# firefly.net
KiCad netlist of a schematic drawn in EAGLE
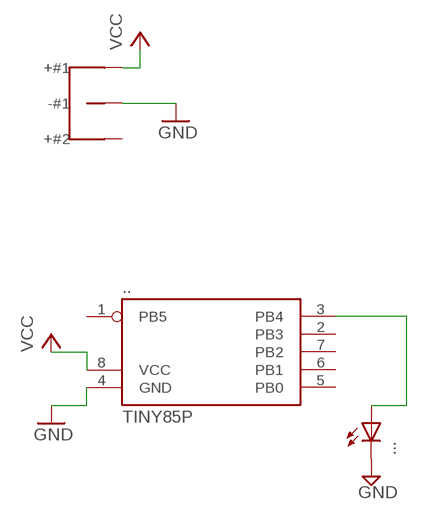
[diagram p0: schematic, sheet 1]

(export (version "E")
  (design (tool "Eeschema 10.0.6"))
  (components
    (comp (ref ".")
      (value "STRAP-BC-2003")
      (footprint "eagle-import:STRAP-BC-2003")
      (libsource (lib "eagle-import") (part "STRAP-BC-2003"))
    )
    (comp (ref "..")
      (value "TINY85P")
      (footprint "eagle-import:DIL08")
      (libsource (lib "eagle-import") (part "TINY85P"))
    )
    (comp (ref "...")
      (value "LED5MM")
      (footprint "eagle-import:LED5MM")
      (libsource (lib "eagle-import") (part "LED5MM"))
    )
  )
  (nets
    (net (code "1") (name "GND") (class "Default")
      (node (ref ".") (pin "-#1") (pinfunction "-#1_-#1") (pintype "bidirectional"))
      (node (ref ".") (pin "-#2") (pinfunction "-#1_-#2") (pintype "bidirectional"))
      (node (ref "..") (pin "4") (pinfunction "GND_4") (pintype "power_in"))
      (node (ref "...") (pin "K") (pinfunction "C_K") (pintype "passive"))
    )
    (net (code "2") (name "Net-(..-PB4)") (class "Default")
      (node (ref "..") (pin "3") (pinfunction "PB4_3") (pintype "bidirectional"))
      (node (ref "...") (pin "A") (pinfunction "A_A") (pintype "passive"))
    )
    (net (code "3") (name "VCC") (class "Default")
      (node (ref ".") (pin "+#1") (pinfunction "+#1_+#1") (pintype "bidirectional"))
      (node (ref "..") (pin "8") (pinfunction "VCC_8") (pintype "power_in"))
    )
    (net (code "4") (name "unconnected-(.-Pad+#2)") (class "Default")
      (node (ref ".") (pin "+#2") (pinfunction "+#2_+#2") (pintype "bidirectional"))
    )
    (net (code "5") (name "unconnected-(..-PB0-Pad5)") (class "Default")
      (node (ref "..") (pin "5") (pinfunction "PB0_5") (pintype "bidirectional"))
    )
    (net (code "6") (name "unconnected-(..-PB1-Pad6)") (class "Default")
      (node (ref "..") (pin "6") (pinfunction "PB1_6") (pintype "bidirectional"))
    )
    (net (code "7") (name "unconnected-(..-PB2-Pad7)") (class "Default")
      (node (ref "..") (pin "7") (pinfunction "PB2_7") (pintype "bidirectional"))
    )
    (net (code "8") (name "unconnected-(..-PB3-Pad2)") (class "Default")
      (node (ref "..") (pin "2") (pinfunction "PB3_2") (pintype "bidirectional"))
    )
    (net (code "9") (name "unconnected-(..-PB5-Pad1)") (class "Default")
      (node (ref "..") (pin "1") (pinfunction "PB5_1") (pintype "bidirectional"))
    )
  )
)
